# mic-preamp-stereo2.net
KiCad netlist of a schematic drawn in EAGLE
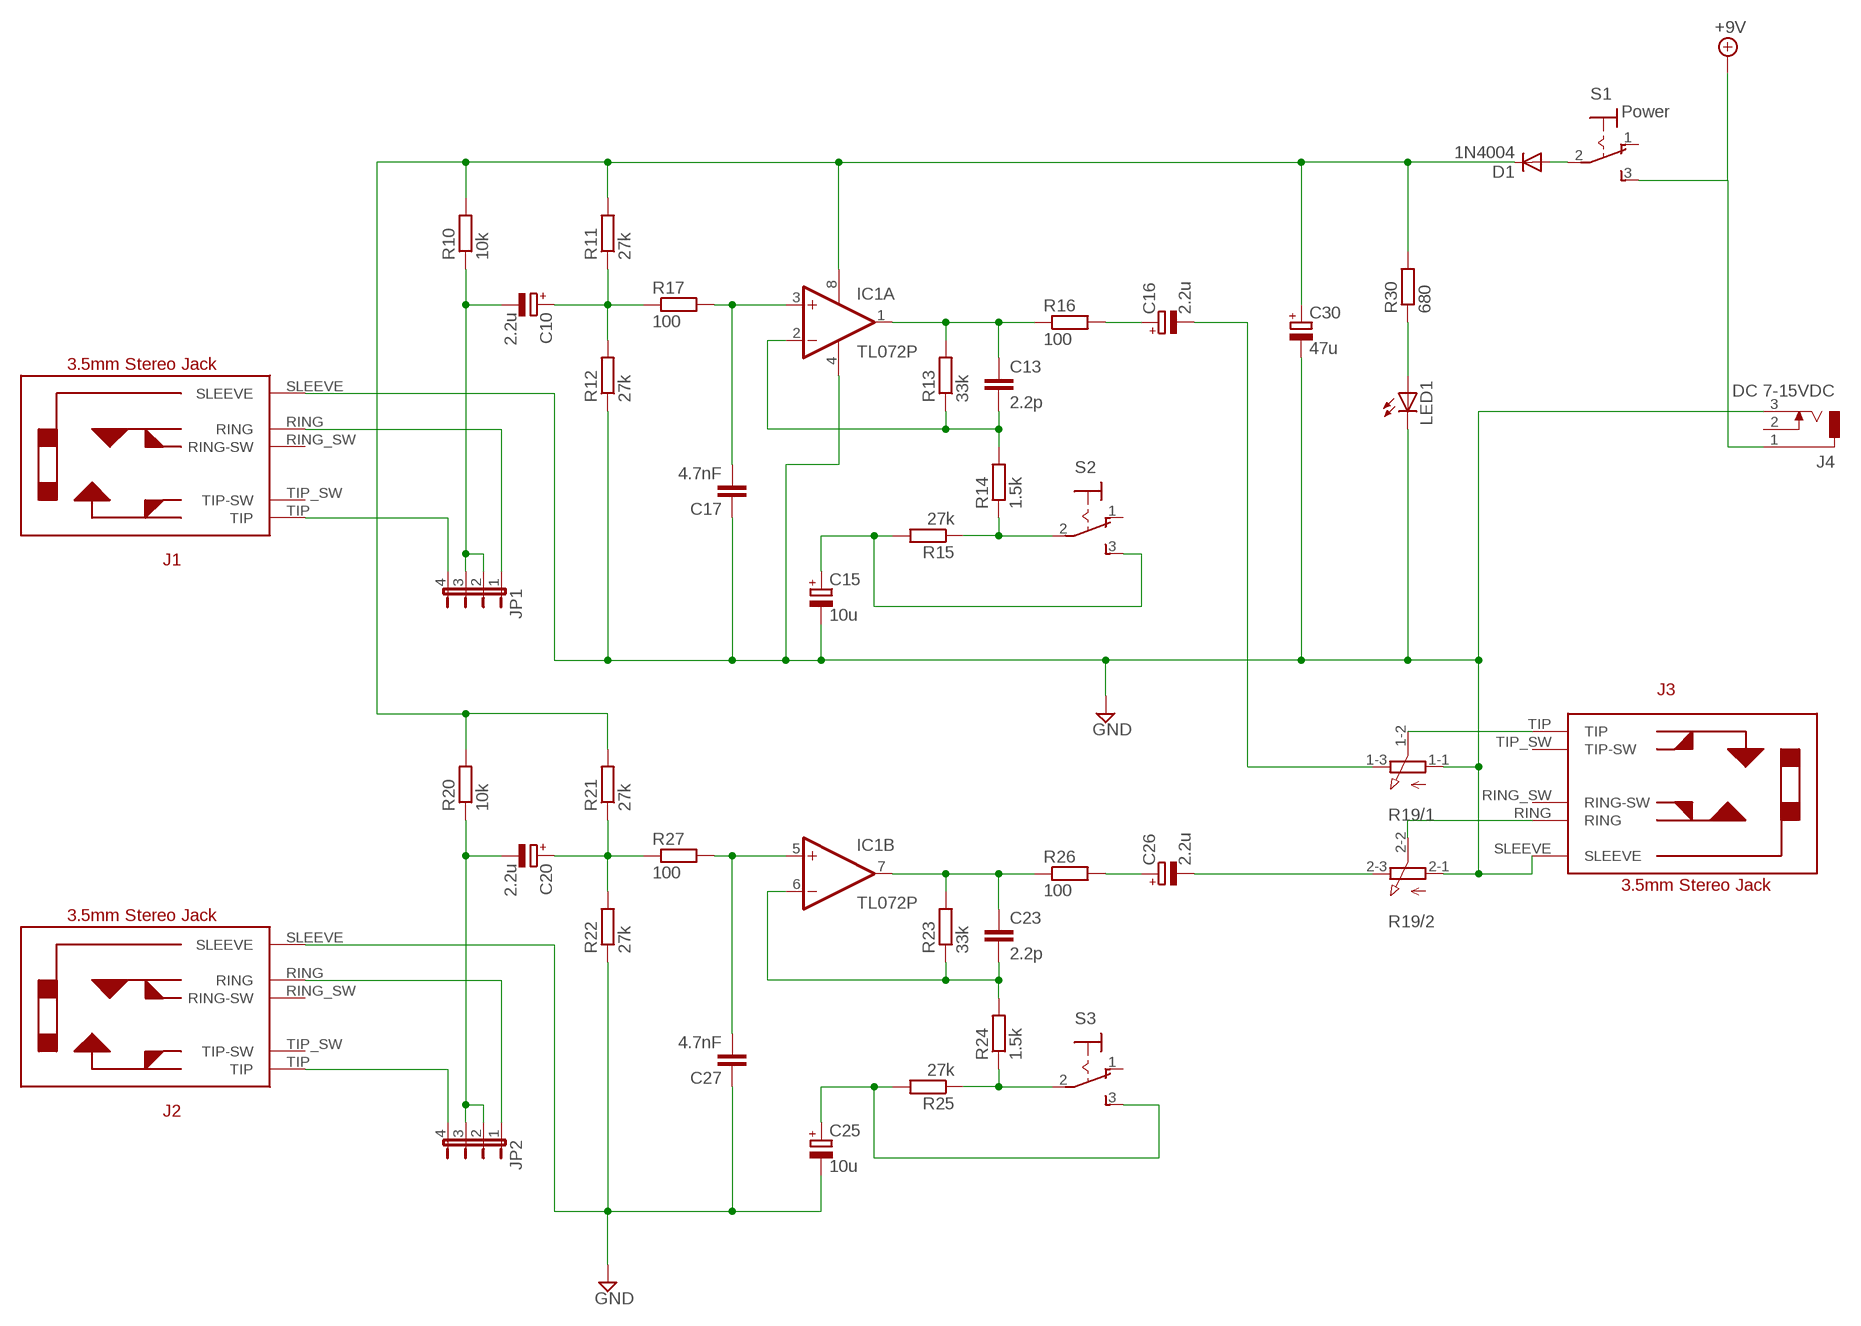
[diagram p0: schematic, sheet 1]

(export (version "E")
  (design (tool "Eeschema 10.0.6"))
  (components
    (comp (ref "C10")
      (value "2.2u")
      (footprint "eagle-import:E2-5")
      (libsource (lib "eagle-import") (part "CPOL-EUE2-5"))
    )
    (comp (ref "C13")
      (value "2.2p")
      (footprint "eagle-import:C025-024X044")
      (libsource (lib "eagle-import") (part "C-EU025-024X044"))
    )
    (comp (ref "C15")
      (value "10u")
      (footprint "eagle-import:E2-5")
      (libsource (lib "eagle-import") (part "CPOL-EUE2-5"))
    )
    (comp (ref "C16")
      (value "2.2u")
      (footprint "eagle-import:E2-5")
      (libsource (lib "eagle-import") (part "CPOL-EUE2-5"))
    )
    (comp (ref "C17")
      (value "4.7nF")
      (footprint "eagle-import:C025-024X044")
      (libsource (lib "eagle-import") (part "C-EU025-024X044"))
    )
    (comp (ref "C20")
      (value "2.2u")
      (footprint "eagle-import:E2-5")
      (libsource (lib "eagle-import") (part "CPOL-EUE2-5"))
    )
    (comp (ref "C23")
      (value "2.2p")
      (footprint "eagle-import:C025-024X044")
      (libsource (lib "eagle-import") (part "C-EU025-024X044"))
    )
    (comp (ref "C25")
      (value "10u")
      (footprint "eagle-import:E2-5")
      (libsource (lib "eagle-import") (part "CPOL-EUE2-5"))
    )
    (comp (ref "C26")
      (value "2.2u")
      (footprint "eagle-import:E2-5")
      (libsource (lib "eagle-import") (part "CPOL-EUE2-5"))
    )
    (comp (ref "C27")
      (value "4.7nF")
      (footprint "eagle-import:C025-024X044")
      (libsource (lib "eagle-import") (part "C-EU025-024X044"))
    )
    (comp (ref "C30")
      (value "47u")
      (footprint "eagle-import:E2-5")
      (libsource (lib "eagle-import") (part "CPOL-EUE2-5"))
    )
    (comp (ref "D1")
      (value "1N4004")
      (footprint "eagle-import:DO41-10")
      (libsource (lib "eagle-import") (part "1N4004"))
    )
    (comp (ref "IC1")
      (value "TL072P")
      (footprint "eagle-import:DIL08")
      (libsource (lib "eagle-import") (part "TL072P"))
    )
    (comp (ref "J1")
      (value "PICAXE_STEREOJACKSOCKET")
      (footprint "eagle-import:PICAXE_STEREOJACKSOCKET")
      (libsource (lib "eagle-import") (part "PICAXE_STEREOJACKSOCKET"))
    )
    (comp (ref "J2")
      (value "PICAXE_STEREOJACKSOCKET")
      (footprint "eagle-import:PICAXE_STEREOJACKSOCKET")
      (libsource (lib "eagle-import") (part "PICAXE_STEREOJACKSOCKET"))
    )
    (comp (ref "J3")
      (value "Stereo Out")
      (footprint "eagle-import:PICAXE_STEREOJACKSOCKET")
      (libsource (lib "eagle-import") (part "PICAXE_STEREOJACKSOCKET"))
    )
    (comp (ref "J4")
      (value "DC 7-15VDC")
      (footprint "eagle-import:DCJ0202")
      (libsource (lib "eagle-import") (part "DCJ0202"))
    )
    (comp (ref "JP1")
      (value "JP4E")
      (footprint "eagle-import:JP4")
      (libsource (lib "eagle-import") (part "JP4E"))
    )
    (comp (ref "JP2")
      (value "JP4E")
      (footprint "eagle-import:JP4")
      (libsource (lib "eagle-import") (part "JP4E"))
    )
    (comp (ref "LED1")
      (value "LED5MM")
      (footprint "eagle-import:LED5MM")
      (libsource (lib "eagle-import") (part "LED5MM"))
    )
    (comp (ref "R10")
      (value "10k")
      (footprint "eagle-import:0207_5V")
      (libsource (lib "eagle-import") (part "R-EU_0207/5V"))
    )
    (comp (ref "R11")
      (value "27k")
      (footprint "eagle-import:0207_5V")
      (libsource (lib "eagle-import") (part "R-EU_0207/5V"))
    )
    (comp (ref "R12")
      (value "27k")
      (footprint "eagle-import:0207_5V")
      (libsource (lib "eagle-import") (part "R-EU_0207/5V"))
    )
    (comp (ref "R13")
      (value "33k")
      (footprint "eagle-import:0207_5V")
      (libsource (lib "eagle-import") (part "R-EU_0207/5V"))
    )
    (comp (ref "R14")
      (value "1.5k")
      (footprint "eagle-import:0207_5V")
      (libsource (lib "eagle-import") (part "R-EU_0207/5V"))
    )
    (comp (ref "R15")
      (value "27k")
      (footprint "eagle-import:0207_5V")
      (libsource (lib "eagle-import") (part "R-EU_0207/5V"))
    )
    (comp (ref "R16")
      (value "100")
      (footprint "eagle-import:0207_5V")
      (libsource (lib "eagle-import") (part "R-EU_0207/5V"))
    )
    (comp (ref "R17")
      (value "100")
      (footprint "eagle-import:0207_5V")
      (libsource (lib "eagle-import") (part "resistor_R-EU_0207/5V"))
    )
    (comp (ref "R19")
      (value "3RP/1610G")
      (footprint "eagle-import:3RP_1610G")
      (libsource (lib "eagle-import") (part "3RP/1610G"))
    )
    (comp (ref "R20")
      (value "10k")
      (footprint "eagle-import:0207_5V")
      (libsource (lib "eagle-import") (part "R-EU_0207/5V"))
    )
    (comp (ref "R21")
      (value "27k")
      (footprint "eagle-import:0207_5V")
      (libsource (lib "eagle-import") (part "R-EU_0207/5V"))
    )
    (comp (ref "R22")
      (value "27k")
      (footprint "eagle-import:0207_5V")
      (libsource (lib "eagle-import") (part "R-EU_0207/5V"))
    )
    (comp (ref "R23")
      (value "33k")
      (footprint "eagle-import:0207_5V")
      (libsource (lib "eagle-import") (part "R-EU_0207/5V"))
    )
    (comp (ref "R24")
      (value "1.5k")
      (footprint "eagle-import:0207_5V")
      (libsource (lib "eagle-import") (part "R-EU_0207/5V"))
    )
    (comp (ref "R25")
      (value "27k")
      (footprint "eagle-import:0207_5V")
      (libsource (lib "eagle-import") (part "R-EU_0207/5V"))
    )
    (comp (ref "R26")
      (value "100")
      (footprint "eagle-import:0207_5V")
      (libsource (lib "eagle-import") (part "R-EU_0207/5V"))
    )
    (comp (ref "R27")
      (value "100")
      (footprint "eagle-import:0207_5V")
      (libsource (lib "eagle-import") (part "resistor_R-EU_0207/5V"))
    )
    (comp (ref "R30")
      (value "680")
      (footprint "eagle-import:0207_12")
      (libsource (lib "eagle-import") (part "R-EU_0207/12"))
    )
    (comp (ref "S1")
      (value "Power")
      (footprint "eagle-import:M9040P")
      (libsource (lib "eagle-import") (part "M9040P"))
    )
    (comp (ref "S2")
      (value "M9040P")
      (footprint "eagle-import:M9040P")
      (libsource (lib "eagle-import") (part "M9040P"))
    )
    (comp (ref "S3")
      (value "M9040P")
      (footprint "eagle-import:M9040P")
      (libsource (lib "eagle-import") (part "M9040P"))
    )
  )
  (nets
    (net (code "1") (name "+9V") (class "Default")
      (node (ref "J4") (pin "1") (pinfunction "1_1") (pintype "passive"))
      (node (ref "S1") (pin "3") (pinfunction "S_3") (pintype "passive"))
    )
    (net (code "2") (name "GND") (class "Default")
      (node (ref "C15") (pin "-") (pinfunction "-_-") (pintype "passive"))
      (node (ref "C17") (pin "1") (pinfunction "1_1") (pintype "passive"))
      (node (ref "C25") (pin "-") (pinfunction "-_-") (pintype "passive"))
      (node (ref "C27") (pin "1") (pinfunction "1_1") (pintype "passive"))
      (node (ref "C30") (pin "-") (pinfunction "-_-") (pintype "passive"))
      (node (ref "IC1") (pin "4") (pinfunction "V-_4") (pintype "power_in"))
      (node (ref "J1") (pin "SLEEVE") (pinfunction "SLEEVE_SLEEVE") (pintype "bidirectional"))
      (node (ref "J2") (pin "SLEEVE") (pinfunction "SLEEVE_SLEEVE") (pintype "bidirectional"))
      (node (ref "J3") (pin "SLEEVE") (pinfunction "SLEEVE_SLEEVE") (pintype "bidirectional"))
      (node (ref "J4") (pin "3") (pinfunction "3_3") (pintype "passive"))
      (node (ref "LED1") (pin "K") (pinfunction "C_K") (pintype "passive"))
      (node (ref "R12") (pin "1") (pinfunction "1_1") (pintype "passive"))
      (node (ref "R19") (pin "1-1") (pinfunction "A_1-1") (pintype "passive"))
      (node (ref "R19") (pin "2-1") (pinfunction "A_2-1") (pintype "passive"))
      (node (ref "R22") (pin "1") (pinfunction "1_1") (pintype "passive"))
    )
    (net (code "3") (name "Net-(C10-Pad+)") (class "Default")
      (node (ref "C10") (pin "+") (pinfunction "+_+") (pintype "passive"))
      (node (ref "R11") (pin "1") (pinfunction "1_1") (pintype "passive"))
      (node (ref "R12") (pin "2") (pinfunction "2_2") (pintype "passive"))
      (node (ref "R17") (pin "1") (pinfunction "1_1") (pintype "passive"))
    )
    (net (code "4") (name "Net-(C10-Pad-)") (class "Default")
      (node (ref "C10") (pin "-") (pinfunction "-_-") (pintype "passive"))
      (node (ref "JP1") (pin "2") (pinfunction "2_2") (pintype "passive"))
      (node (ref "JP1") (pin "3") (pinfunction "3_3") (pintype "passive"))
      (node (ref "R10") (pin "1") (pinfunction "1_1") (pintype "passive"))
    )
    (net (code "5") (name "Net-(C16-Pad+)") (class "Default")
      (node (ref "C16") (pin "+") (pinfunction "+_+") (pintype "passive"))
      (node (ref "R16") (pin "2") (pinfunction "2_2") (pintype "passive"))
    )
    (net (code "6") (name "Net-(C20-Pad+)") (class "Default")
      (node (ref "C20") (pin "+") (pinfunction "+_+") (pintype "passive"))
      (node (ref "R21") (pin "1") (pinfunction "1_1") (pintype "passive"))
      (node (ref "R22") (pin "2") (pinfunction "2_2") (pintype "passive"))
      (node (ref "R27") (pin "1") (pinfunction "1_1") (pintype "passive"))
    )
    (net (code "7") (name "Net-(C20-Pad-)") (class "Default")
      (node (ref "C20") (pin "-") (pinfunction "-_-") (pintype "passive"))
      (node (ref "JP2") (pin "2") (pinfunction "2_2") (pintype "passive"))
      (node (ref "JP2") (pin "3") (pinfunction "3_3") (pintype "passive"))
      (node (ref "R20") (pin "1") (pinfunction "1_1") (pintype "passive"))
    )
    (net (code "8") (name "Net-(C26-Pad+)") (class "Default")
      (node (ref "C26") (pin "+") (pinfunction "+_+") (pintype "passive"))
      (node (ref "R26") (pin "2") (pinfunction "2_2") (pintype "passive"))
    )
    (net (code "9") (name "Net-(IC1A-+IN)") (class "Default")
      (node (ref "C17") (pin "2") (pinfunction "2_2") (pintype "passive"))
      (node (ref "IC1") (pin "3") (pinfunction "+IN_3") (pintype "input"))
      (node (ref "R17") (pin "2") (pinfunction "2_2") (pintype "passive"))
    )
    (net (code "10") (name "Net-(IC1A--IN)") (class "Default")
      (node (ref "C13") (pin "2") (pinfunction "2_2") (pintype "passive"))
      (node (ref "IC1") (pin "2") (pinfunction "-IN_2") (pintype "input"))
      (node (ref "R13") (pin "1") (pinfunction "1_1") (pintype "passive"))
      (node (ref "R14") (pin "2") (pinfunction "2_2") (pintype "passive"))
    )
    (net (code "11") (name "Net-(IC1A-OUT)") (class "Default")
      (node (ref "C13") (pin "1") (pinfunction "1_1") (pintype "passive"))
      (node (ref "IC1") (pin "1") (pinfunction "OUT_1") (pintype "output"))
      (node (ref "R13") (pin "2") (pinfunction "2_2") (pintype "passive"))
      (node (ref "R16") (pin "1") (pinfunction "1_1") (pintype "passive"))
    )
    (net (code "12") (name "Net-(IC1B-+IN)") (class "Default")
      (node (ref "C27") (pin "2") (pinfunction "2_2") (pintype "passive"))
      (node (ref "IC1") (pin "5") (pinfunction "+IN_5") (pintype "input"))
      (node (ref "R27") (pin "2") (pinfunction "2_2") (pintype "passive"))
    )
    (net (code "13") (name "Net-(IC1B--IN)") (class "Default")
      (node (ref "C23") (pin "2") (pinfunction "2_2") (pintype "passive"))
      (node (ref "IC1") (pin "6") (pinfunction "-IN_6") (pintype "input"))
      (node (ref "R23") (pin "1") (pinfunction "1_1") (pintype "passive"))
      (node (ref "R24") (pin "2") (pinfunction "2_2") (pintype "passive"))
    )
    (net (code "14") (name "Net-(IC1B-OUT)") (class "Default")
      (node (ref "C23") (pin "1") (pinfunction "1_1") (pintype "passive"))
      (node (ref "IC1") (pin "7") (pinfunction "OUT_7") (pintype "output"))
      (node (ref "R23") (pin "2") (pinfunction "2_2") (pintype "passive"))
      (node (ref "R26") (pin "1") (pinfunction "1_1") (pintype "passive"))
    )
    (net (code "15") (name "Net-(IC1C-V+)") (class "Default")
      (node (ref "C30") (pin "+") (pinfunction "+_+") (pintype "passive"))
      (node (ref "D1") (pin "C") (pinfunction "C_C") (pintype "passive"))
      (node (ref "IC1") (pin "8") (pinfunction "V+_8") (pintype "power_in"))
      (node (ref "R10") (pin "2") (pinfunction "2_2") (pintype "passive"))
      (node (ref "R11") (pin "2") (pinfunction "2_2") (pintype "passive"))
      (node (ref "R20") (pin "2") (pinfunction "2_2") (pintype "passive"))
      (node (ref "R21") (pin "2") (pinfunction "2_2") (pintype "passive"))
      (node (ref "R30") (pin "2") (pinfunction "2_2") (pintype "passive"))
    )
    (net (code "16") (name "Net-(J1-PadRING)") (class "Default")
      (node (ref "J1") (pin "RING") (pinfunction "RING_RING") (pintype "bidirectional"))
      (node (ref "JP1") (pin "1") (pinfunction "1_1") (pintype "passive"))
    )
    (net (code "17") (name "Net-(J1-PadTIP)") (class "Default")
      (node (ref "J1") (pin "TIP") (pinfunction "TIP_TIP") (pintype "bidirectional"))
      (node (ref "JP1") (pin "4") (pinfunction "4_4") (pintype "passive"))
    )
    (net (code "18") (name "Net-(J2-PadRING)") (class "Default")
      (node (ref "J2") (pin "RING") (pinfunction "RING_RING") (pintype "bidirectional"))
      (node (ref "JP2") (pin "1") (pinfunction "1_1") (pintype "passive"))
    )
    (net (code "19") (name "Net-(J2-PadTIP)") (class "Default")
      (node (ref "J2") (pin "TIP") (pinfunction "TIP_TIP") (pintype "bidirectional"))
      (node (ref "JP2") (pin "4") (pinfunction "4_4") (pintype "passive"))
    )
    (net (code "20") (name "Net-(LED1-PadA)") (class "Default")
      (node (ref "LED1") (pin "A") (pinfunction "A_A") (pintype "passive"))
      (node (ref "R30") (pin "1") (pinfunction "1_1") (pintype "passive"))
    )
    (net (code "21") (name "Net-(R19A-E)") (class "Default")
      (node (ref "C16") (pin "-") (pinfunction "-_-") (pintype "passive"))
      (node (ref "R19") (pin "1-3") (pinfunction "E_1-3") (pintype "passive"))
    )
    (net (code "22") (name "Net-(R19A-S)") (class "Default")
      (node (ref "J3") (pin "TIP") (pinfunction "TIP_TIP") (pintype "bidirectional"))
      (node (ref "R19") (pin "1-2") (pinfunction "S_1-2") (pintype "passive"))
    )
    (net (code "23") (name "Net-(R19B-E)") (class "Default")
      (node (ref "C26") (pin "-") (pinfunction "-_-") (pintype "passive"))
      (node (ref "R19") (pin "2-3") (pinfunction "E_2-3") (pintype "passive"))
    )
    (net (code "24") (name "Net-(R19B-S)") (class "Default")
      (node (ref "J3") (pin "RING") (pinfunction "RING_RING") (pintype "bidirectional"))
      (node (ref "R19") (pin "2-2") (pinfunction "S_2-2") (pintype "passive"))
    )
    (net (code "25") (name "Net-(S1-P)") (class "Default")
      (node (ref "D1") (pin "A") (pinfunction "A_A") (pintype "passive"))
      (node (ref "S1") (pin "2") (pinfunction "P_2") (pintype "passive"))
    )
    (net (code "26") (name "Net-(S2-P)") (class "Default")
      (node (ref "R14") (pin "1") (pinfunction "1_1") (pintype "passive"))
      (node (ref "R15") (pin "1") (pinfunction "1_1") (pintype "passive"))
      (node (ref "S2") (pin "2") (pinfunction "P_2") (pintype "passive"))
    )
    (net (code "27") (name "Net-(S2-S)") (class "Default")
      (node (ref "C15") (pin "+") (pinfunction "+_+") (pintype "passive"))
      (node (ref "R15") (pin "2") (pinfunction "2_2") (pintype "passive"))
      (node (ref "S2") (pin "3") (pinfunction "S_3") (pintype "passive"))
    )
    (net (code "28") (name "Net-(S3-P)") (class "Default")
      (node (ref "R24") (pin "1") (pinfunction "1_1") (pintype "passive"))
      (node (ref "R25") (pin "1") (pinfunction "1_1") (pintype "passive"))
      (node (ref "S3") (pin "2") (pinfunction "P_2") (pintype "passive"))
    )
    (net (code "29") (name "Net-(S3-S)") (class "Default")
      (node (ref "C25") (pin "+") (pinfunction "+_+") (pintype "passive"))
      (node (ref "R25") (pin "2") (pinfunction "2_2") (pintype "passive"))
      (node (ref "S3") (pin "3") (pinfunction "S_3") (pintype "passive"))
    )
    (net (code "30") (name "unconnected-(J1-RING-SW-PadRING_SW)") (class "Default")
      (node (ref "J1") (pin "RING_SW") (pinfunction "RING-SW_RING_SW") (pintype "bidirectional"))
    )
    (net (code "31") (name "unconnected-(J1-TIP-SW-PadTIP_SW)") (class "Default")
      (node (ref "J1") (pin "TIP_SW") (pinfunction "TIP-SW_TIP_SW") (pintype "bidirectional"))
    )
    (net (code "32") (name "unconnected-(J2-RING-SW-PadRING_SW)") (class "Default")
      (node (ref "J2") (pin "RING_SW") (pinfunction "RING-SW_RING_SW") (pintype "bidirectional"))
    )
    (net (code "33") (name "unconnected-(J2-TIP-SW-PadTIP_SW)") (class "Default")
      (node (ref "J2") (pin "TIP_SW") (pinfunction "TIP-SW_TIP_SW") (pintype "bidirectional"))
    )
    (net (code "34") (name "unconnected-(J3-RING-SW-PadRING_SW)") (class "Default")
      (node (ref "J3") (pin "RING_SW") (pinfunction "RING-SW_RING_SW") (pintype "bidirectional"))
    )
    (net (code "35") (name "unconnected-(J3-TIP-SW-PadTIP_SW)") (class "Default")
      (node (ref "J3") (pin "TIP_SW") (pinfunction "TIP-SW_TIP_SW") (pintype "bidirectional"))
    )
    (net (code "36") (name "unconnected-(J4-Pad2)") (class "Default")
      (node (ref "J4") (pin "2") (pinfunction "2_2") (pintype "passive"))
    )
    (net (code "37") (name "unconnected-(S1-O-Pad1)") (class "Default")
      (node (ref "S1") (pin "1") (pinfunction "O_1") (pintype "passive"))
    )
    (net (code "38") (name "unconnected-(S2-O-Pad1)") (class "Default")
      (node (ref "S2") (pin "1") (pinfunction "O_1") (pintype "passive"))
    )
    (net (code "39") (name "unconnected-(S3-O-Pad1)") (class "Default")
      (node (ref "S3") (pin "1") (pinfunction "O_1") (pintype "passive"))
    )
  )
)
